# MicroMod_STM32_Processor.net
KiCad netlist of a schematic drawn in EAGLE
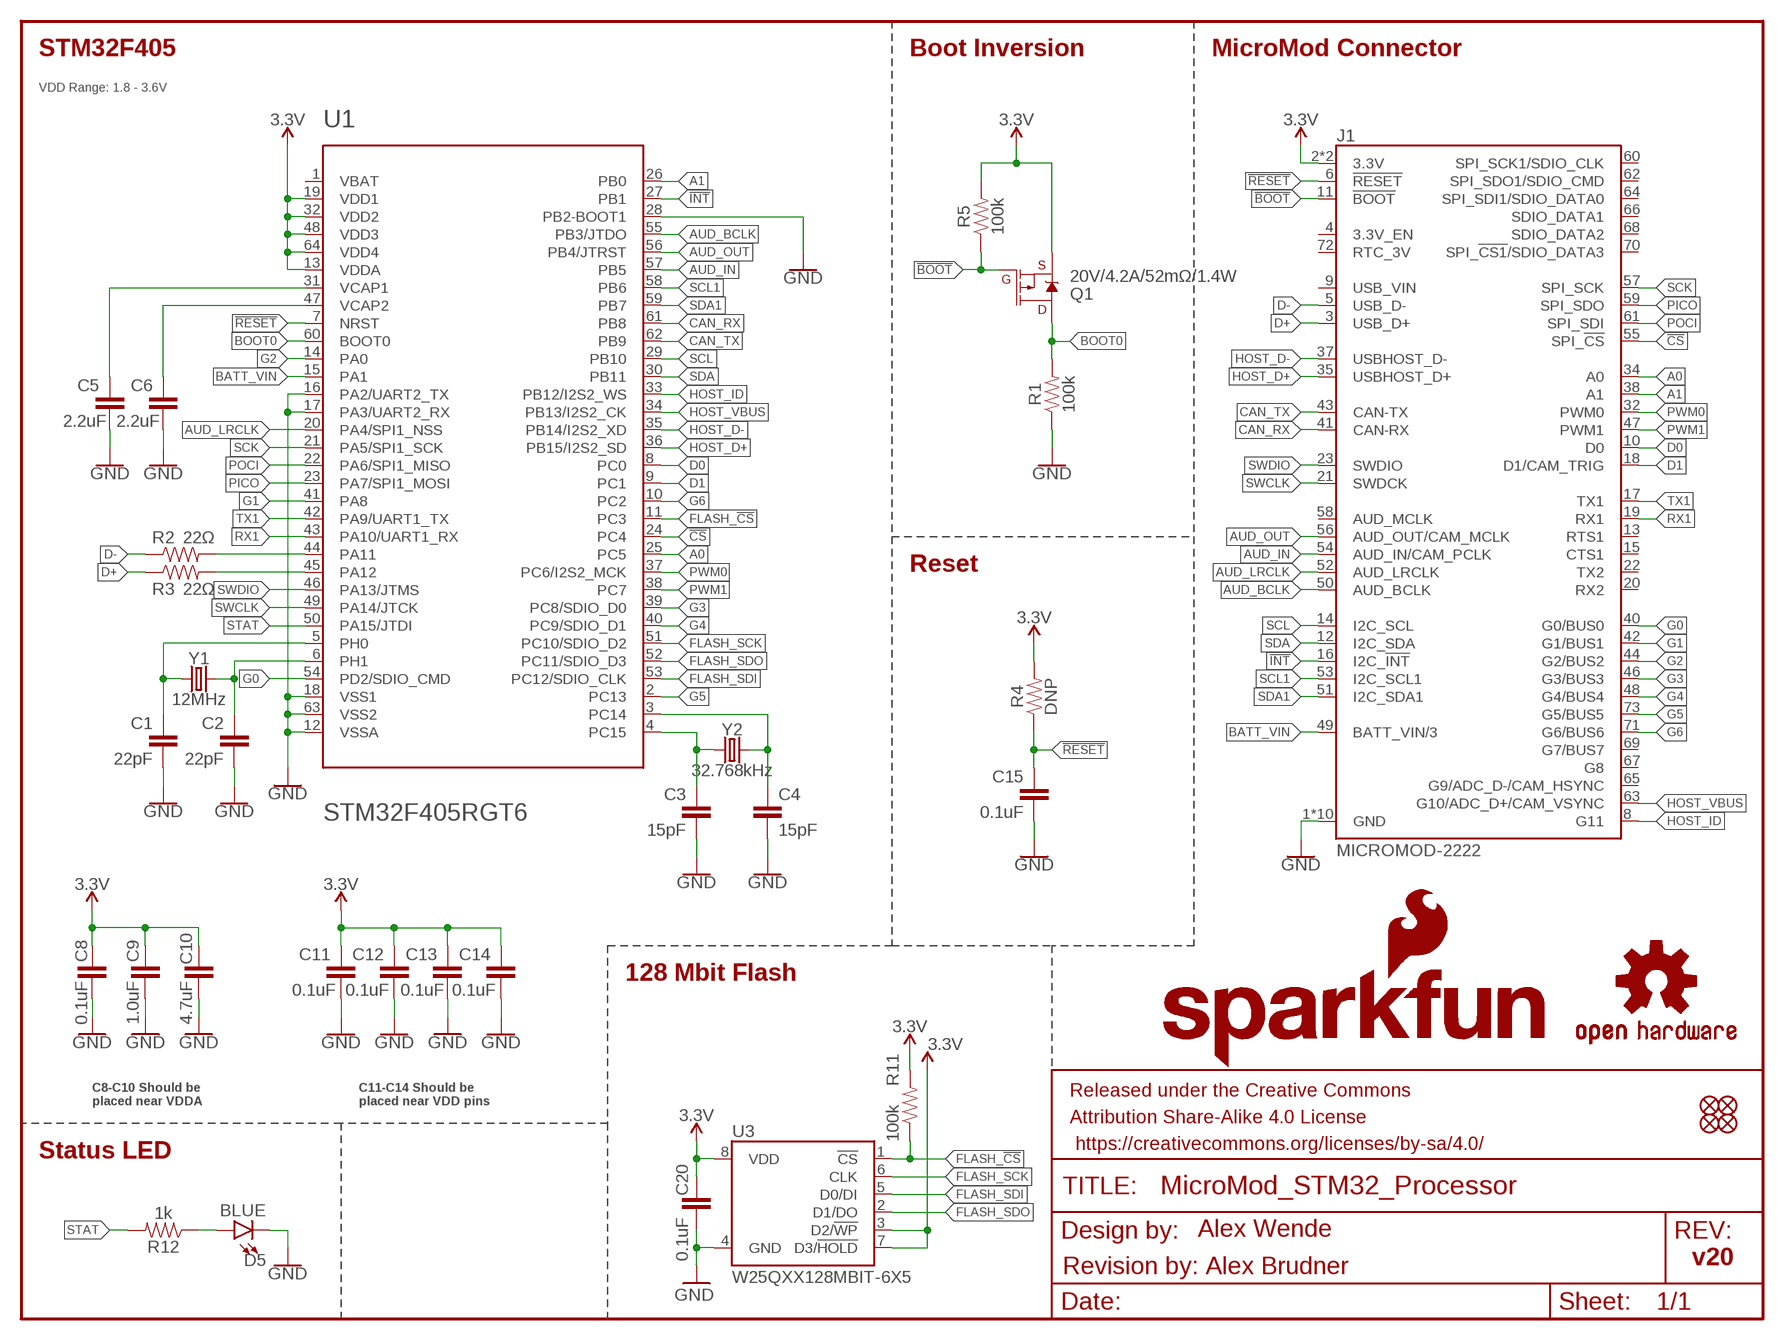
[diagram p0: schematic, sheet 1]

(export (version "E")
  (design (tool "Eeschema 10.0.6"))
  (components
    (comp (ref "C1")
      (value "22pF")
      (footprint "eagle-import:0402-TIGHT")
      (libsource (lib "eagle-import") (part "22PF-0402T-16V-10%"))
    )
    (comp (ref "C2")
      (value "22pF")
      (footprint "eagle-import:0402-TIGHT")
      (libsource (lib "eagle-import") (part "22PF-0402T-16V-10%"))
    )
    (comp (ref "C3")
      (value "15pF")
      (footprint "eagle-import:0402-TIGHT")
      (libsource (lib "eagle-import") (part "15PF-0402T-50V-5%"))
    )
    (comp (ref "C4")
      (value "15pF")
      (footprint "eagle-import:0402-TIGHT")
      (libsource (lib "eagle-import") (part "15PF-0402T-50V-5%"))
    )
    (comp (ref "C5")
      (value "2.2uF")
      (footprint "eagle-import:0402-TIGHT")
      (libsource (lib "eagle-import") (part "2.2UF-0402_TIGHT-10V-10%-X5R"))
    )
    (comp (ref "C6")
      (value "2.2uF")
      (footprint "eagle-import:0402-TIGHT")
      (libsource (lib "eagle-import") (part "2.2UF-0402_TIGHT-10V-10%-X5R"))
    )
    (comp (ref "C8")
      (value "0.1uF")
      (footprint "eagle-import:0402-TIGHT")
      (fields (field (name "SPICEPREFIX") "C"))
      (libsource (lib "eagle-import") (part "0.1UF-0402T-10V-10%-X7R"))
    )
    (comp (ref "C9")
      (value "1.0uF")
      (footprint "eagle-import:0402-TIGHT")
      (fields (field (name "SPICEPREFIX") "C"))
      (libsource (lib "eagle-import") (part "1.0UF-0402T-16V-10%"))
    )
    (comp (ref "C10")
      (value "4.7uF")
      (footprint "eagle-import:0402-TIGHT")
      (fields (field (name "SPICEPREFIX") "C"))
      (libsource (lib "eagle-import") (part "4.7UF-0402_TIGHT-6.3V-20%-X5R"))
    )
    (comp (ref "C11")
      (value "0.1uF")
      (footprint "eagle-import:0402-TIGHT")
      (libsource (lib "eagle-import") (part "0.1UF-0402T-10V-10%-X7R"))
    )
    (comp (ref "C12")
      (value "0.1uF")
      (footprint "eagle-import:0402-TIGHT")
      (libsource (lib "eagle-import") (part "0.1UF-0402T-10V-10%-X7R"))
    )
    (comp (ref "C13")
      (value "0.1uF")
      (footprint "eagle-import:0402-TIGHT")
      (libsource (lib "eagle-import") (part "0.1UF-0402T-10V-10%-X7R"))
    )
    (comp (ref "C14")
      (value "0.1uF")
      (footprint "eagle-import:0402-TIGHT")
      (libsource (lib "eagle-import") (part "0.1UF-0402T-10V-10%-X7R"))
    )
    (comp (ref "C15")
      (value "0.1uF")
      (footprint "eagle-import:0402-TIGHT")
      (libsource (lib "eagle-import") (part "0.1UF-0402T-10V-10%-X7R"))
    )
    (comp (ref "C20")
      (value "0.1uF")
      (footprint "eagle-import:0402-TIGHT")
      (libsource (lib "eagle-import") (part "0.1UF-0402T-10V-10%-X7R"))
    )
    (comp (ref "D5")
      (value "BLUE")
      (footprint "eagle-import:LED-0603")
      (libsource (lib "eagle-import") (part "LED-BLUE0603"))
    )
    (comp (ref "FD1")
      (value "FIDUCIALUFIDUCIAL")
      (footprint "eagle-import:FIDUCIAL-MICRO")
      (libsource (lib "eagle-import") (part "FIDUCIALUFIDUCIAL"))
    )
    (comp (ref "FD2")
      (value "FIDUCIALUFIDUCIAL")
      (footprint "eagle-import:FIDUCIAL-MICRO")
      (libsource (lib "eagle-import") (part "FIDUCIALUFIDUCIAL"))
    )
    (comp (ref "FD3")
      (value "FIDUCIALUFIDUCIAL")
      (footprint "eagle-import:FIDUCIAL-MICRO")
      (libsource (lib "eagle-import") (part "FIDUCIALUFIDUCIAL"))
    )
    (comp (ref "FD4")
      (value "FIDUCIALUFIDUCIAL")
      (footprint "eagle-import:FIDUCIAL-MICRO")
      (libsource (lib "eagle-import") (part "FIDUCIALUFIDUCIAL"))
    )
    (comp (ref "FRAME1")
      (value "FRAME-LETTER")
      (footprint "eagle-import:CREATIVE_COMMONS")
      (libsource (lib "eagle-import") (part "FRAME-LETTER"))
    )
    (comp (ref "J1")
      (value "MICROMOD-2222")
      (footprint "eagle-import:M.2-CARD-E-22")
      (libsource (lib "eagle-import") (part "MICROMOD-2222"))
    )
    (comp (ref "LOGO2")
      (value "OSHW-LOGOS")
      (footprint "eagle-import:OSHW-LOGO-S")
      (libsource (lib "eagle-import") (part "OSHW-LOGOS"))
    )
    (comp (ref "LOGO3")
      (value "SFE_LOGO_NAME_FLAME.1_INCH")
      (footprint "eagle-import:SFE_LOGO_NAME_FLAME_.1")
      (libsource (lib "eagle-import") (part "SFE_LOGO_NAME_FLAME.1_INCH"))
    )
    (comp (ref "Q1")
      (value "20V/4.2A/52mΩ/1.4W")
      (footprint "eagle-import:SOT23-3")
      (libsource (lib "eagle-import") (part "MOSFET_PCH-DMG2305UX-7"))
    )
    (comp (ref "R1")
      (value "100k")
      (footprint "eagle-import:0402-TIGHT")
      (libsource (lib "eagle-import") (part "100KOHM-0402T-1/16W-1%"))
    )
    (comp (ref "R2")
      (value "22Ω")
      (footprint "eagle-import:0402-TIGHT")
      (libsource (lib "eagle-import") (part "22OHM-0402T-1/16W-1%"))
    )
    (comp (ref "R3")
      (value "22Ω")
      (footprint "eagle-import:0402-TIGHT")
      (libsource (lib "eagle-import") (part "22OHM-0402T-1/16W-1%"))
    )
    (comp (ref "R4")
      (value "DNP")
      (footprint "eagle-import:0402-TIGHT_NO_CREAM")
      (libsource (lib "eagle-import") (part "DNP-0402T_NO_CREAM"))
    )
    (comp (ref "R5")
      (value "100k")
      (footprint "eagle-import:0402-TIGHT")
      (libsource (lib "eagle-import") (part "100KOHM-0402T-1/16W-1%"))
    )
    (comp (ref "R11")
      (value "100k")
      (footprint "eagle-import:0402-TIGHT")
      (libsource (lib "eagle-import") (part "100KOHM-0402T-1/16W-1%"))
    )
    (comp (ref "R12")
      (value "1k")
      (footprint "eagle-import:0402-TIGHT")
      (libsource (lib "eagle-import") (part "1KOHM-0402T-1/16W-1%"))
    )
    (comp (ref "U1")
      (value "STM32F405RGT6")
      (footprint "eagle-import:TQFP64")
      (libsource (lib "eagle-import") (part "STM32F405RG_LOGICAL"))
    )
    (comp (ref "U3")
      (value "W25QXX128MBIT-6X5")
      (footprint "eagle-import:WSON-8-6X5")
      (libsource (lib "eagle-import") (part "W25QXX128MBIT-6X5"))
    )
    (comp (ref "Y1")
      (value "12MHz")
      (footprint "eagle-import:CRYSTAL-SMD-5X3.2-4PAD")
      (libsource (lib "eagle-import") (part "CRYSTAL-12MHZ{dblquote}"))
    )
    (comp (ref "Y2")
      (value "32.768kHz")
      (footprint "eagle-import:CRYSTAL-SMD-3.2X1.5MM")
      (libsource (lib "eagle-import") (part "CRYSTAL-32.768KHZSMD-3.2X1.5"))
    )
  )
  (nets
    (net (code "1") (name "/FLASH_~{CS}") (class "Default")
      (node (ref "R11") (pin "1") (pinfunction "1_1") (pintype "passive"))
      (node (ref "U1") (pin "11") (pinfunction "PC3_11") (pintype "bidirectional"))
      (node (ref "U3") (pin "1") (pinfunction "~{CS}_1") (pintype "bidirectional"))
    )
    (net (code "2") (name "/~{BOOT}") (class "Default")
      (node (ref "J1") (pin "11") (pinfunction "~{BOOT}_11") (pintype "bidirectional"))
      (node (ref "Q1") (pin "1") (pinfunction "G_1") (pintype "bidirectional"))
      (node (ref "R5") (pin "1") (pinfunction "1_1") (pintype "passive"))
    )
    (net (code "3") (name "/~{CS}") (class "Default")
      (node (ref "J1") (pin "55") (pinfunction "SPI_~{CS}_55") (pintype "bidirectional"))
      (node (ref "U1") (pin "24") (pinfunction "PC4_24") (pintype "bidirectional"))
    )
    (net (code "4") (name "/~{INT}") (class "Default")
      (node (ref "J1") (pin "16") (pinfunction "I2C_~{INT}_16") (pintype "bidirectional"))
      (node (ref "U1") (pin "27") (pinfunction "PB1_27") (pintype "bidirectional"))
    )
    (net (code "5") (name "/~{RESET}") (class "Default")
      (node (ref "C15") (pin "1") (pinfunction "1_1") (pintype "passive"))
      (node (ref "J1") (pin "6") (pinfunction "~{RESET}_6") (pintype "bidirectional"))
      (node (ref "R4") (pin "1") (pinfunction "1_1") (pintype "passive"))
      (node (ref "U1") (pin "7") (pinfunction "NRST_7") (pintype "bidirectional"))
    )
    (net (code "6") (name "3.3V") (class "Default")
      (node (ref "C10") (pin "1") (pinfunction "1_1") (pintype "passive"))
      (node (ref "C11") (pin "1") (pinfunction "1_1") (pintype "passive"))
      (node (ref "C12") (pin "1") (pinfunction "1_1") (pintype "passive"))
      (node (ref "C13") (pin "1") (pinfunction "1_1") (pintype "passive"))
      (node (ref "C14") (pin "1") (pinfunction "1_1") (pintype "passive"))
      (node (ref "C20") (pin "1") (pinfunction "1_1") (pintype "passive"))
      (node (ref "C8") (pin "1") (pinfunction "1_1") (pintype "passive"))
      (node (ref "C9") (pin "1") (pinfunction "1_1") (pintype "passive"))
      (node (ref "J1") (pin "2") (pinfunction "3.3V_2") (pintype "bidirectional"))
      (node (ref "J1") (pin "74") (pinfunction "3.3V_74") (pintype "bidirectional"))
      (node (ref "Q1") (pin "2") (pinfunction "S_2") (pintype "bidirectional"))
      (node (ref "R11") (pin "2") (pinfunction "2_2") (pintype "passive"))
      (node (ref "R4") (pin "2") (pinfunction "2_2") (pintype "passive"))
      (node (ref "R5") (pin "2") (pinfunction "2_2") (pintype "passive"))
      (node (ref "U1") (pin "13") (pinfunction "VDDA_13") (pintype "bidirectional"))
      (node (ref "U1") (pin "19") (pinfunction "VDD1_19") (pintype "bidirectional"))
      (node (ref "U1") (pin "32") (pinfunction "VDD2_32") (pintype "bidirectional"))
      (node (ref "U1") (pin "48") (pinfunction "VDD3_48") (pintype "bidirectional"))
      (node (ref "U1") (pin "64") (pinfunction "VDD4_64") (pintype "bidirectional"))
      (node (ref "U3") (pin "3") (pinfunction "D2/~{WP}_3") (pintype "bidirectional"))
      (node (ref "U3") (pin "7") (pinfunction "D3/~{HOLD}_7") (pintype "bidirectional"))
      (node (ref "U3") (pin "8") (pinfunction "VDD_8") (pintype "bidirectional"))
    )
    (net (code "7") (name "A0") (class "Default")
      (node (ref "J1") (pin "34") (pinfunction "A0_34") (pintype "bidirectional"))
      (node (ref "U1") (pin "25") (pinfunction "PC5_25") (pintype "bidirectional"))
    )
    (net (code "8") (name "A1") (class "Default")
      (node (ref "J1") (pin "38") (pinfunction "A1_38") (pintype "bidirectional"))
      (node (ref "U1") (pin "26") (pinfunction "PB0_26") (pintype "bidirectional"))
    )
    (net (code "9") (name "AUD_BCLK") (class "Default")
      (node (ref "J1") (pin "50") (pinfunction "AUD_BCLK_50") (pintype "bidirectional"))
      (node (ref "U1") (pin "55") (pinfunction "PB3/JTDO_55") (pintype "bidirectional"))
    )
    (net (code "10") (name "AUD_IN") (class "Default")
      (node (ref "J1") (pin "54") (pinfunction "AUD_IN/CAM_PCLK_54") (pintype "bidirectional"))
      (node (ref "U1") (pin "57") (pinfunction "PB5_57") (pintype "bidirectional"))
    )
    (net (code "11") (name "AUD_LRCLK") (class "Default")
      (node (ref "J1") (pin "52") (pinfunction "AUD_LRCLK_52") (pintype "bidirectional"))
      (node (ref "U1") (pin "20") (pinfunction "PA4/SPI1_NSS_20") (pintype "bidirectional"))
    )
    (net (code "12") (name "AUD_OUT") (class "Default")
      (node (ref "J1") (pin "56") (pinfunction "AUD_OUT/CAM_MCLK_56") (pintype "bidirectional"))
      (node (ref "U1") (pin "56") (pinfunction "PB4/JTRST_56") (pintype "bidirectional"))
    )
    (net (code "13") (name "BATT_VIN") (class "Default")
      (node (ref "J1") (pin "49") (pinfunction "BATT_VIN/3_49") (pintype "bidirectional"))
      (node (ref "U1") (pin "15") (pinfunction "PA1_15") (pintype "bidirectional"))
    )
    (net (code "14") (name "BOOT0") (class "Default")
      (node (ref "Q1") (pin "3") (pinfunction "D_3") (pintype "bidirectional"))
      (node (ref "R1") (pin "2") (pinfunction "2_2") (pintype "passive"))
      (node (ref "U1") (pin "60") (pinfunction "BOOT0_60") (pintype "bidirectional"))
    )
    (net (code "15") (name "CAN_RX") (class "Default")
      (node (ref "J1") (pin "41") (pinfunction "CAN-RX_41") (pintype "bidirectional"))
      (node (ref "U1") (pin "61") (pinfunction "PB8_61") (pintype "bidirectional"))
    )
    (net (code "16") (name "CAN_TX") (class "Default")
      (node (ref "J1") (pin "43") (pinfunction "CAN-TX_43") (pintype "bidirectional"))
      (node (ref "U1") (pin "62") (pinfunction "PB9_62") (pintype "bidirectional"))
    )
    (net (code "17") (name "D+") (class "Default")
      (node (ref "J1") (pin "3") (pinfunction "USB_D+_3") (pintype "bidirectional"))
      (node (ref "R3") (pin "1") (pinfunction "1_1") (pintype "passive"))
    )
    (net (code "18") (name "D-") (class "Default")
      (node (ref "J1") (pin "5") (pinfunction "USB_D-_5") (pintype "bidirectional"))
      (node (ref "R2") (pin "1") (pinfunction "1_1") (pintype "passive"))
    )
    (net (code "19") (name "D0") (class "Default")
      (node (ref "J1") (pin "10") (pinfunction "D0_10") (pintype "bidirectional"))
      (node (ref "U1") (pin "8") (pinfunction "PC0_8") (pintype "bidirectional"))
    )
    (net (code "20") (name "D1") (class "Default")
      (node (ref "J1") (pin "18") (pinfunction "D1/CAM_TRIG_18") (pintype "bidirectional"))
      (node (ref "U1") (pin "9") (pinfunction "PC1_9") (pintype "bidirectional"))
    )
    (net (code "21") (name "FLASH_SCK") (class "Default")
      (node (ref "U1") (pin "51") (pinfunction "PC10/SDIO_D2_51") (pintype "bidirectional"))
      (node (ref "U3") (pin "6") (pinfunction "CLK_6") (pintype "bidirectional"))
    )
    (net (code "22") (name "FLASH_SDI") (class "Default")
      (node (ref "U1") (pin "53") (pinfunction "PC12/SDIO_CLK_53") (pintype "bidirectional"))
      (node (ref "U3") (pin "5") (pinfunction "D0/DI_5") (pintype "bidirectional"))
    )
    (net (code "23") (name "FLASH_SDO") (class "Default")
      (node (ref "U1") (pin "52") (pinfunction "PC11/SDIO_D3_52") (pintype "bidirectional"))
      (node (ref "U3") (pin "2") (pinfunction "D1/DO_2") (pintype "bidirectional"))
    )
    (net (code "24") (name "G0") (class "Default")
      (node (ref "J1") (pin "40") (pinfunction "G0/BUS0_40") (pintype "bidirectional"))
      (node (ref "U1") (pin "54") (pinfunction "PD2/SDIO_CMD_54") (pintype "bidirectional"))
    )
    (net (code "25") (name "G1") (class "Default")
      (node (ref "J1") (pin "42") (pinfunction "G1/BUS1_42") (pintype "bidirectional"))
      (node (ref "U1") (pin "41") (pinfunction "PA8_41") (pintype "bidirectional"))
    )
    (net (code "26") (name "G2") (class "Default")
      (node (ref "J1") (pin "44") (pinfunction "G2/BUS2_44") (pintype "bidirectional"))
      (node (ref "U1") (pin "14") (pinfunction "PA0_14") (pintype "bidirectional"))
    )
    (net (code "27") (name "G3") (class "Default")
      (node (ref "J1") (pin "46") (pinfunction "G3/BUS3_46") (pintype "bidirectional"))
      (node (ref "U1") (pin "39") (pinfunction "PC8/SDIO_D0_39") (pintype "bidirectional"))
    )
    (net (code "28") (name "G4") (class "Default")
      (node (ref "J1") (pin "48") (pinfunction "G4/BUS4_48") (pintype "bidirectional"))
      (node (ref "U1") (pin "40") (pinfunction "PC9/SDIO_D1_40") (pintype "bidirectional"))
    )
    (net (code "29") (name "G5") (class "Default")
      (node (ref "J1") (pin "73") (pinfunction "G5/BUS5_73") (pintype "bidirectional"))
      (node (ref "U1") (pin "2") (pinfunction "PC13_2") (pintype "bidirectional"))
    )
    (net (code "30") (name "G6") (class "Default")
      (node (ref "J1") (pin "71") (pinfunction "G6/BUS6_71") (pintype "bidirectional"))
      (node (ref "U1") (pin "10") (pinfunction "PC2_10") (pintype "bidirectional"))
    )
    (net (code "31") (name "GND") (class "Default")
      (node (ref "C1") (pin "2") (pinfunction "2_2") (pintype "passive"))
      (node (ref "C10") (pin "2") (pinfunction "2_2") (pintype "passive"))
      (node (ref "C11") (pin "2") (pinfunction "2_2") (pintype "passive"))
      (node (ref "C12") (pin "2") (pinfunction "2_2") (pintype "passive"))
      (node (ref "C13") (pin "2") (pinfunction "2_2") (pintype "passive"))
      (node (ref "C14") (pin "2") (pinfunction "2_2") (pintype "passive"))
      (node (ref "C15") (pin "2") (pinfunction "2_2") (pintype "passive"))
      (node (ref "C2") (pin "2") (pinfunction "2_2") (pintype "passive"))
      (node (ref "C20") (pin "2") (pinfunction "2_2") (pintype "passive"))
      (node (ref "C3") (pin "2") (pinfunction "2_2") (pintype "passive"))
      (node (ref "C4") (pin "2") (pinfunction "2_2") (pintype "passive"))
      (node (ref "C5") (pin "2") (pinfunction "2_2") (pintype "passive"))
      (node (ref "C6") (pin "2") (pinfunction "2_2") (pintype "passive"))
      (node (ref "C8") (pin "2") (pinfunction "2_2") (pintype "passive"))
      (node (ref "C9") (pin "2") (pinfunction "2_2") (pintype "passive"))
      (node (ref "D5") (pin "C") (pinfunction "C_C") (pintype "passive"))
      (node (ref "J1") (pin "1") (pinfunction "GND_1") (pintype "bidirectional"))
      (node (ref "J1") (pin "33") (pinfunction "GND_33") (pintype "bidirectional"))
      (node (ref "J1") (pin "36") (pinfunction "GND_36") (pintype "bidirectional"))
      (node (ref "J1") (pin "39") (pinfunction "GND_39") (pintype "bidirectional"))
      (node (ref "J1") (pin "45") (pinfunction "GND_45") (pintype "bidirectional"))
      (node (ref "J1") (pin "7") (pinfunction "GND_7") (pintype "bidirectional"))
      (node (ref "J1") (pin "75") (pinfunction "GND_75") (pintype "bidirectional"))
      (node (ref "J1") (pin "GND1") (pinfunction "GND_GND1") (pintype "bidirectional"))
      (node (ref "J1") (pin "GND2") (pinfunction "GND_GND2") (pintype "bidirectional"))
      (node (ref "J1") (pin "GND3") (pinfunction "GND_GND3") (pintype "bidirectional"))
      (node (ref "R1") (pin "1") (pinfunction "1_1") (pintype "passive"))
      (node (ref "U1") (pin "12") (pinfunction "VSSA_12") (pintype "bidirectional"))
      (node (ref "U1") (pin "16") (pinfunction "PA2/UART2_TX_16") (pintype "bidirectional"))
      (node (ref "U1") (pin "17") (pinfunction "PA3/UART2_RX_17") (pintype "bidirectional"))
      (node (ref "U1") (pin "18") (pinfunction "VSS1_18") (pintype "bidirectional"))
      (node (ref "U1") (pin "28") (pinfunction "PB2-BOOT1_28") (pintype "bidirectional"))
      (node (ref "U1") (pin "63") (pinfunction "VSS2_63") (pintype "bidirectional"))
      (node (ref "U3") (pin "4") (pinfunction "GND_4") (pintype "bidirectional"))
    )
    (net (code "32") (name "HOST_D+") (class "Default")
      (node (ref "J1") (pin "35") (pinfunction "USBHOST_D+_35") (pintype "bidirectional"))
      (node (ref "U1") (pin "36") (pinfunction "PB15/I2S2_SD_36") (pintype "bidirectional"))
    )
    (net (code "33") (name "HOST_D-") (class "Default")
      (node (ref "J1") (pin "37") (pinfunction "USBHOST_D-_37") (pintype "bidirectional"))
      (node (ref "U1") (pin "35") (pinfunction "PB14/I2S2_XD_35") (pintype "bidirectional"))
    )
    (net (code "34") (name "HOST_ID") (class "Default")
      (node (ref "J1") (pin "8") (pinfunction "G11_8") (pintype "bidirectional"))
      (node (ref "U1") (pin "33") (pinfunction "PB12/I2S2_WS_33") (pintype "bidirectional"))
    )
    (net (code "35") (name "HOST_VBUS") (class "Default")
      (node (ref "J1") (pin "63") (pinfunction "G10/ADC_D+/CAM_VSYNC_63") (pintype "bidirectional"))
      (node (ref "U1") (pin "34") (pinfunction "PB13/I2S2_CK_34") (pintype "bidirectional"))
    )
    (net (code "36") (name "Net-(D5-PadA)") (class "Default")
      (node (ref "D5") (pin "A") (pinfunction "A_A") (pintype "passive"))
      (node (ref "R12") (pin "1") (pinfunction "1_1") (pintype "passive"))
    )
    (net (code "37") (name "Net-(U1-PA11)") (class "Default")
      (node (ref "R2") (pin "2") (pinfunction "2_2") (pintype "passive"))
      (node (ref "U1") (pin "44") (pinfunction "PA11_44") (pintype "bidirectional"))
    )
    (net (code "38") (name "Net-(U1-PA12)") (class "Default")
      (node (ref "R3") (pin "2") (pinfunction "2_2") (pintype "passive"))
      (node (ref "U1") (pin "45") (pinfunction "PA12_45") (pintype "bidirectional"))
    )
    (net (code "39") (name "Net-(U1-PC14)") (class "Default")
      (node (ref "C4") (pin "1") (pinfunction "1_1") (pintype "passive"))
      (node (ref "U1") (pin "3") (pinfunction "PC14_3") (pintype "bidirectional"))
      (node (ref "Y2") (pin "P$2") (pinfunction "2_P$2") (pintype "passive"))
    )
    (net (code "40") (name "Net-(U1-PC15)") (class "Default")
      (node (ref "C3") (pin "1") (pinfunction "1_1") (pintype "passive"))
      (node (ref "U1") (pin "4") (pinfunction "PC15_4") (pintype "bidirectional"))
      (node (ref "Y2") (pin "P$1") (pinfunction "1_P$1") (pintype "passive"))
    )
    (net (code "41") (name "Net-(U1-PH0)") (class "Default")
      (node (ref "C1") (pin "1") (pinfunction "1_1") (pintype "passive"))
      (node (ref "U1") (pin "5") (pinfunction "PH0_5") (pintype "bidirectional"))
      (node (ref "Y1") (pin "1") (pinfunction "1_1") (pintype "passive"))
    )
    (net (code "42") (name "Net-(U1-PH1)") (class "Default")
      (node (ref "C2") (pin "1") (pinfunction "1_1") (pintype "passive"))
      (node (ref "U1") (pin "6") (pinfunction "PH1_6") (pintype "bidirectional"))
      (node (ref "Y1") (pin "3") (pinfunction "2_3") (pintype "passive"))
    )
    (net (code "43") (name "Net-(U1-VCAP1)") (class "Default")
      (node (ref "C5") (pin "1") (pinfunction "1_1") (pintype "passive"))
      (node (ref "U1") (pin "31") (pinfunction "VCAP1_31") (pintype "bidirectional"))
    )
    (net (code "44") (name "Net-(U1-VCAP2)") (class "Default")
      (node (ref "C6") (pin "1") (pinfunction "1_1") (pintype "passive"))
      (node (ref "U1") (pin "47") (pinfunction "VCAP2_47") (pintype "bidirectional"))
    )
    (net (code "45") (name "PICO") (class "Default")
      (node (ref "J1") (pin "59") (pinfunction "SPI_SDO_59") (pintype "bidirectional"))
      (node (ref "U1") (pin "23") (pinfunction "PA7/SPI1_MOSI_23") (pintype "bidirectional"))
    )
    (net (code "46") (name "POCI") (class "Default")
      (node (ref "J1") (pin "61") (pinfunction "SPI_SDI_61") (pintype "bidirectional"))
      (node (ref "U1") (pin "22") (pinfunction "PA6/SPI1_MISO_22") (pintype "bidirectional"))
    )
    (net (code "47") (name "PWM0") (class "Default")
      (node (ref "J1") (pin "32") (pinfunction "PWM0_32") (pintype "bidirectional"))
      (node (ref "U1") (pin "37") (pinfunction "PC6/I2S2_MCK_37") (pintype "bidirectional"))
    )
    (net (code "48") (name "PWM1") (class "Default")
      (node (ref "J1") (pin "47") (pinfunction "PWM1_47") (pintype "bidirectional"))
      (node (ref "U1") (pin "38") (pinfunction "PC7_38") (pintype "bidirectional"))
    )
    (net (code "49") (name "RX1") (class "Default")
      (node (ref "J1") (pin "19") (pinfunction "RX1_19") (pintype "bidirectional"))
      (node (ref "U1") (pin "43") (pinfunction "PA10/UART1_RX_43") (pintype "bidirectional"))
    )
    (net (code "50") (name "SCK") (class "Default")
      (node (ref "J1") (pin "57") (pinfunction "SPI_SCK_57") (pintype "bidirectional"))
      (node (ref "U1") (pin "21") (pinfunction "PA5/SPI1_SCK_21") (pintype "bidirectional"))
    )
    (net (code "51") (name "SCL") (class "Default")
      (node (ref "J1") (pin "14") (pinfunction "I2C_SCL_14") (pintype "bidirectional"))
      (node (ref "U1") (pin "29") (pinfunction "PB10_29") (pintype "bidirectional"))
    )
    (net (code "52") (name "SCL1") (class "Default")
      (node (ref "J1") (pin "53") (pinfunction "I2C_SCL1_53") (pintype "bidirectional"))
      (node (ref "U1") (pin "58") (pinfunction "PB6_58") (pintype "bidirectional"))
    )
    (net (code "53") (name "SDA") (class "Default")
      (node (ref "J1") (pin "12") (pinfunction "I2C_SDA_12") (pintype "bidirectional"))
      (node (ref "U1") (pin "30") (pinfunction "PB11_30") (pintype "bidirectional"))
    )
    (net (code "54") (name "SDA1") (class "Default")
      (node (ref "J1") (pin "51") (pinfunction "I2C_SDA1_51") (pintype "bidirectional"))
      (node (ref "U1") (pin "59") (pinfunction "PB7_59") (pintype "bidirectional"))
    )
    (net (code "55") (name "STAT") (class "Default")
      (node (ref "R12") (pin "2") (pinfunction "2_2") (pintype "passive"))
      (node (ref "U1") (pin "50") (pinfunction "PA15/JTDI_50") (pintype "bidirectional"))
    )
    (net (code "56") (name "SWCLK") (class "Default")
      (node (ref "J1") (pin "21") (pinfunction "SWDCK_21") (pintype "bidirectional"))
      (node (ref "U1") (pin "49") (pinfunction "PA14/JTCK_49") (pintype "bidirectional"))
    )
    (net (code "57") (name "SWDIO") (class "Default")
      (node (ref "J1") (pin "23") (pinfunction "SWDIO_23") (pintype "bidirectional"))
      (node (ref "U1") (pin "46") (pinfunction "PA13/JTMS_46") (pintype "bidirectional"))
    )
    (net (code "58") (name "TX1") (class "Default")
      (node (ref "J1") (pin "17") (pinfunction "TX1_17") (pintype "bidirectional"))
      (node (ref "U1") (pin "42") (pinfunction "PA9/UART1_TX_42") (pintype "bidirectional"))
    )
    (net (code "59") (name "unconnected-(J1-3.3V_EN-Pad4)") (class "Default")
      (node (ref "J1") (pin "4") (pinfunction "3.3V_EN_4") (pintype "bidirectional"))
    )
    (net (code "60") (name "unconnected-(J1-AUD_MCLK-Pad58)") (class "Default")
      (node (ref "J1") (pin "58") (pinfunction "AUD_MCLK_58") (pintype "bidirectional"))
    )
    (net (code "61") (name "unconnected-(J1-CTS1-Pad15)") (class "Default")
      (node (ref "J1") (pin "15") (pinfunction "CTS1_15") (pintype "bidirectional"))
    )
    (net (code "62") (name "unconnected-(J1-G7{slash}BUS7-Pad69)") (class "Default")
      (node (ref "J1") (pin "69") (pinfunction "G7/BUS7_69") (pintype "bidirectional"))
    )
    (net (code "63") (name "unconnected-(J1-G8-Pad67)") (class "Default")
      (node (ref "J1") (pin "67") (pinfunction "G8_67") (pintype "bidirectional"))
    )
    (net (code "64") (name "unconnected-(J1-G9{slash}ADC_D-{slash}CAM_HSYNC-Pad65)") (class "Default")
      (node (ref "J1") (pin "65") (pinfunction "G9/ADC_D-/CAM_HSYNC_65") (pintype "bidirectional"))
    )
    (net (code "65") (name "unconnected-(J1-RTC_3V-Pad72)") (class "Default")
      (node (ref "J1") (pin "72") (pinfunction "RTC_3V_72") (pintype "bidirectional"))
    )
    (net (code "66") (name "unconnected-(J1-RTS1-Pad13)") (class "Default")
      (node (ref "J1") (pin "13") (pinfunction "RTS1_13") (pintype "bidirectional"))
    )
    (net (code "67") (name "unconnected-(J1-RX2-Pad20)") (class "Default")
      (node (ref "J1") (pin "20") (pinfunction "RX2_20") (pintype "bidirectional"))
    )
    (net (code "68") (name "unconnected-(J1-SDIO_DATA1-Pad66)") (class "Default")
      (node (ref "J1") (pin "66") (pinfunction "SDIO_DATA1_66") (pintype "bidirectional"))
    )
    (net (code "69") (name "unconnected-(J1-SDIO_DATA2-Pad68)") (class "Default")
      (node (ref "J1") (pin "68") (pinfunction "SDIO_DATA2_68") (pintype "bidirectional"))
    )
    (net (code "70") (name "unconnected-(J1-SPI_SCK1{slash}SDIO_CLK-Pad60)") (class "Default")
      (node (ref "J1") (pin "60") (pinfunction "SPI_SCK1/SDIO_CLK_60") (pintype "bidirectional"))
    )
    (net (code "71") (name "unconnected-(J1-SPI_SDI1{slash}SDIO_DATA0-Pad64)") (class "Default")
      (node (ref "J1") (pin "64") (pinfunction "SPI_SDI1/SDIO_DATA0_64") (pintype "bidirectional"))
    )
    (net (code "72") (name "unconnected-(J1-SPI_SDO1{slash}SDIO_CMD-Pad62)") (class "Default")
      (node (ref "J1") (pin "62") (pinfunction "SPI_SDO1/SDIO_CMD_62") (pintype "bidirectional"))
    )
    (net (code "73") (name "unconnected-(J1-SPI_~{CS1}{slash}SDIO_DATA3-Pad70)") (class "Default")
      (node (ref "J1") (pin "70") (pinfunction "SPI_~{CS1}/SDIO_DATA3_70") (pintype "bidirectional"))
    )
    (net (code "74") (name "unconnected-(J1-TX2-Pad22)") (class "Default")
      (node (ref "J1") (pin "22") (pinfunction "TX2_22") (pintype "bidirectional"))
    )
    (net (code "75") (name "unconnected-(J1-USB_VIN-Pad9)") (class "Default")
      (node (ref "J1") (pin "9") (pinfunction "USB_VIN_9") (pintype "bidirectional"))
    )
    (net (code "76") (name "unconnected-(U1-VBAT-Pad1)") (class "Default")
      (node (ref "U1") (pin "1") (pinfunction "VBAT_1") (pintype "bidirectional"))
    )
  )
)
